# Memory.net
KiCad netlist of a schematic drawn in Altium Designer
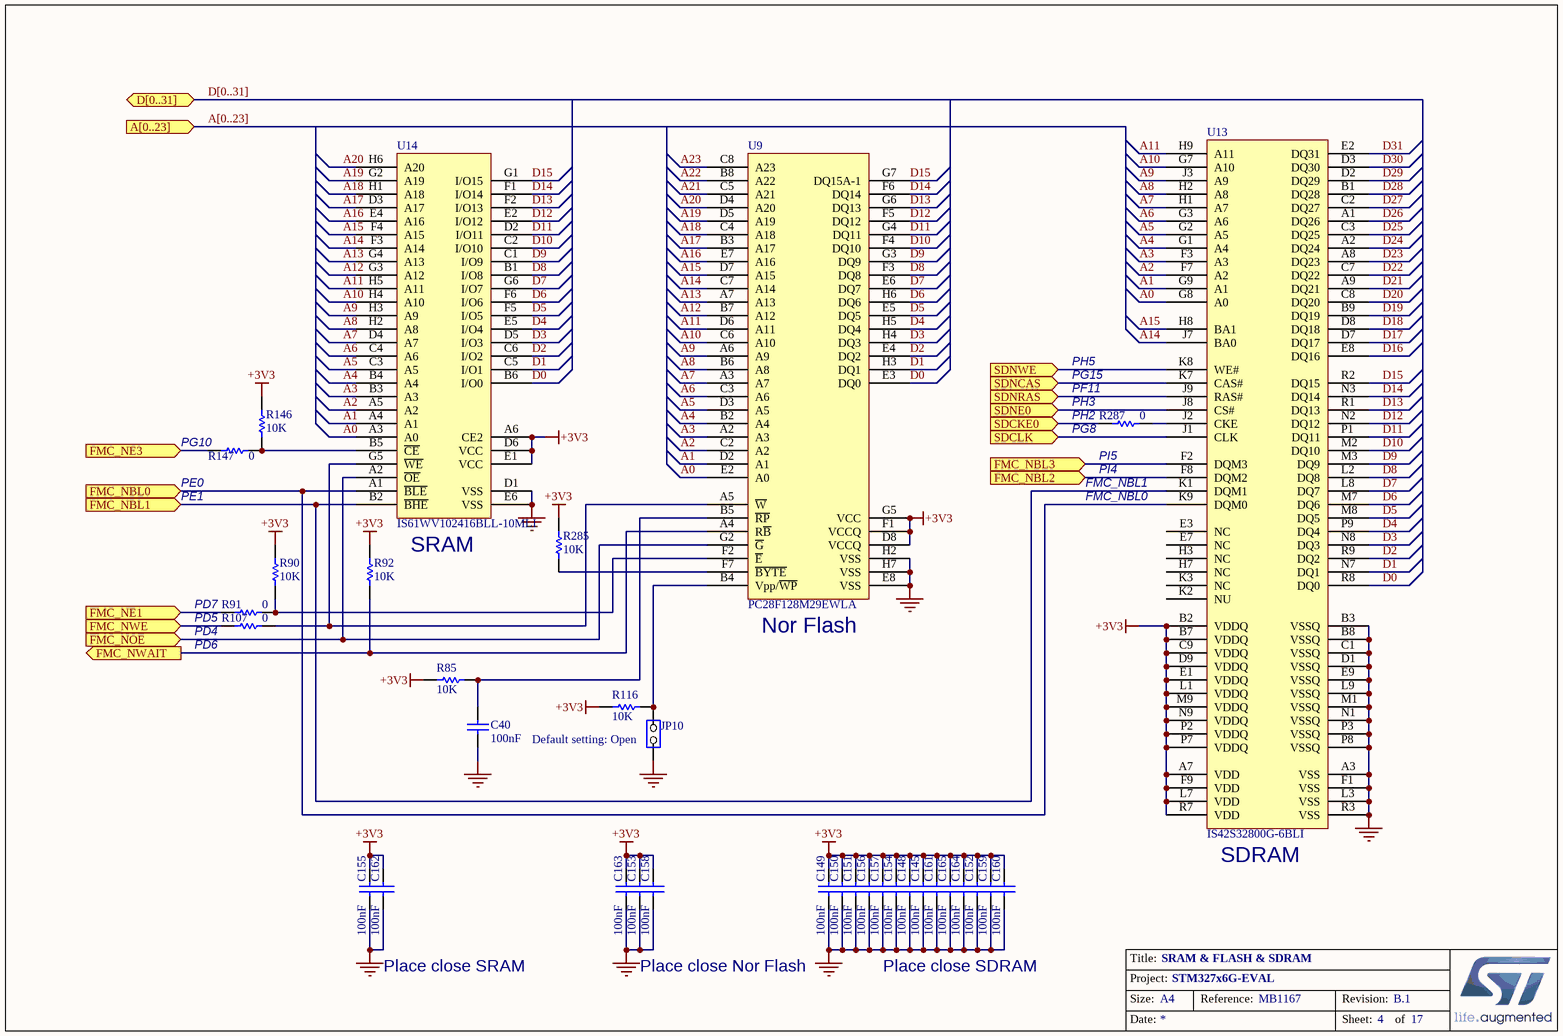
[diagram p0: Memory.SchDoc]

(export (version "E")
  (design (tool "Eeschema 10.0.6"))
  (components
    (comp (ref "C40")
      (value "100nF")
      (footprint "0603C")
      (description "Capacitor")
      (fields (field (name "PUBLISHER") "Altium Limited"))
      (libsource (lib "Miscellaneous Devices") (part "Cap"))
    )
    (comp (ref "C145")
      (value "100nF")
      (footprint "0603C")
      (description "Capacitor")
      (fields (field (name "PUBLISHER") "Altium Limited"))
      (libsource (lib "Miscellaneous Devices") (part "Cap"))
    )
    (comp (ref "C148")
      (value "100nF")
      (footprint "0603C")
      (description "Capacitor")
      (fields (field (name "PUBLISHER") "Altium Limited"))
      (libsource (lib "Miscellaneous Devices") (part "Cap"))
    )
    (comp (ref "C149")
      (value "100nF")
      (footprint "0603C")
      (description "Capacitor")
      (fields (field (name "PUBLISHER") "Altium Limited"))
      (libsource (lib "Miscellaneous Devices") (part "Cap"))
    )
    (comp (ref "C150")
      (value "100nF")
      (footprint "0603C")
      (description "Capacitor")
      (fields (field (name "PUBLISHER") "Altium Limited"))
      (libsource (lib "Miscellaneous Devices") (part "Cap"))
    )
    (comp (ref "C151")
      (value "100nF")
      (footprint "0603C")
      (description "Capacitor")
      (fields (field (name "PUBLISHER") "Altium Limited"))
      (libsource (lib "Miscellaneous Devices") (part "Cap"))
    )
    (comp (ref "C152")
      (value "100nF")
      (footprint "0603C")
      (description "Capacitor")
      (fields (field (name "PUBLISHER") "Altium Limited"))
      (libsource (lib "Miscellaneous Devices") (part "Cap"))
    )
    (comp (ref "C153")
      (value "100nF")
      (footprint "0603C")
      (description "Capacitor")
      (fields (field (name "PUBLISHER") "Altium Limited"))
      (libsource (lib "Miscellaneous Devices") (part "Cap"))
    )
    (comp (ref "C154")
      (value "100nF")
      (footprint "0603C")
      (description "Capacitor")
      (fields (field (name "PUBLISHER") "Altium Limited"))
      (libsource (lib "Miscellaneous Devices") (part "Cap"))
    )
    (comp (ref "C155")
      (value "100nF")
      (footprint "0603C")
      (description "Capacitor")
      (fields (field (name "PUBLISHER") "Altium Limited"))
      (libsource (lib "Miscellaneous Devices") (part "Cap"))
    )
    (comp (ref "C156")
      (value "100nF")
      (footprint "0603C")
      (description "Capacitor")
      (fields (field (name "PUBLISHER") "Altium Limited"))
      (libsource (lib "Miscellaneous Devices") (part "Cap"))
    )
    (comp (ref "C157")
      (value "100nF")
      (footprint "0603C")
      (description "Capacitor")
      (fields (field (name "PUBLISHER") "Altium Limited"))
      (libsource (lib "Miscellaneous Devices") (part "Cap"))
    )
    (comp (ref "C158")
      (value "100nF")
      (footprint "0603C")
      (description "Capacitor")
      (fields (field (name "PUBLISHER") "Altium Limited"))
      (libsource (lib "Miscellaneous Devices") (part "Cap"))
    )
    (comp (ref "C159")
      (value "100nF")
      (footprint "0603C")
      (description "Capacitor")
      (fields (field (name "PUBLISHER") "Altium Limited"))
      (libsource (lib "Miscellaneous Devices") (part "Cap"))
    )
    (comp (ref "C160")
      (value "100nF")
      (footprint "0603C")
      (description "Capacitor")
      (fields (field (name "PUBLISHER") "Altium Limited"))
      (libsource (lib "Miscellaneous Devices") (part "Cap"))
    )
    (comp (ref "C161")
      (value "100nF")
      (footprint "0603C")
      (description "Capacitor")
      (fields (field (name "PUBLISHER") "Altium Limited"))
      (libsource (lib "Miscellaneous Devices") (part "Cap"))
    )
    (comp (ref "C162")
      (value "100nF")
      (footprint "0603C")
      (description "Capacitor")
      (fields (field (name "PUBLISHER") "Altium Limited"))
      (libsource (lib "Miscellaneous Devices") (part "Cap"))
    )
    (comp (ref "C163")
      (value "100nF")
      (footprint "0603C")
      (description "Capacitor")
      (fields (field (name "PUBLISHER") "Altium Limited"))
      (libsource (lib "Miscellaneous Devices") (part "Cap"))
    )
    (comp (ref "C164")
      (value "100nF")
      (footprint "0603C")
      (description "Capacitor")
      (fields (field (name "PUBLISHER") "Altium Limited"))
      (libsource (lib "Miscellaneous Devices") (part "Cap"))
    )
    (comp (ref "C165")
      (value "100nF")
      (footprint "0603C")
      (description "Capacitor")
      (fields (field (name "PUBLISHER") "Altium Limited"))
      (libsource (lib "Miscellaneous Devices") (part "Cap"))
    )
    (comp (ref "JP10") (value "~") (footprint "SIP2") (libsource (lib "*") (part "JP2")))
    (comp (ref "R85")
      (value "10K")
      (footprint "0603R")
      (description "Resistor")
      (fields (field (name "PUBLISHER") "Altium Limited"))
      (libsource (lib "Miscellaneous Devices") (part "Res1"))
    )
    (comp (ref "R90")
      (value "10K")
      (footprint "0603R")
      (description "Resistor")
      (fields (field (name "PUBLISHER") "Altium Limited"))
      (libsource (lib "Miscellaneous Devices") (part "Res1"))
    )
    (comp (ref "R91")
      (value "0")
      (footprint "0603R")
      (description "Resistor")
      (fields (field (name "PUBLISHER") "Altium Limited"))
      (libsource (lib "Miscellaneous Devices") (part "Res1"))
    )
    (comp (ref "R92")
      (value "10K")
      (footprint "0603R")
      (description "Resistor")
      (fields (field (name "PUBLISHER") "Altium Limited"))
      (libsource (lib "Miscellaneous Devices") (part "Res1"))
    )
    (comp (ref "R107")
      (value "0")
      (footprint "0603R")
      (description "Resistor")
      (fields (field (name "PUBLISHER") "Altium Limited"))
      (libsource (lib "Miscellaneous Devices") (part "Res1"))
    )
    (comp (ref "R116")
      (value "10K")
      (footprint "0603R")
      (description "Resistor")
      (fields (field (name "PUBLISHER") "Altium Limited"))
      (libsource (lib "Miscellaneous Devices") (part "Res1"))
    )
    (comp (ref "R146")
      (value "10K")
      (footprint "0603R")
      (description "Resistor")
      (fields (field (name "PUBLISHER") "Altium Limited"))
      (libsource (lib "Miscellaneous Devices") (part "Res1"))
    )
    (comp (ref "R147")
      (value "0")
      (footprint "0603R")
      (description "Resistor")
      (fields (field (name "PUBLISHER") "Altium Limited"))
      (libsource (lib "Miscellaneous Devices") (part "Res1"))
    )
    (comp (ref "R285")
      (value "10K")
      (footprint "0603R")
      (description "Resistor")
      (fields (field (name "PUBLISHER") "Altium Limited"))
      (libsource (lib "Miscellaneous Devices") (part "Res1"))
    )
    (comp (ref "R287")
      (value "0")
      (footprint "0603R")
      (description "Resistor")
      (fields (field (name "PUBLISHER") "Altium Limited"))
      (libsource (lib "Miscellaneous Devices") (part "Res1"))
    )
    (comp (ref "U9")
      (value "PC28F128M29EWLA")
      (footprint "FBGA64_1_11X13")
      (libsource (lib "MB964") (part "M29W128FL70ZA6E"))
    )
    (comp (ref "U13")
      (value "IS42S32800G-6BLI")
      (footprint "FBGA90_0R8_8X13")
      (libsource (lib "mb1045") (part "MT48LC4M32B2B5"))
    )
    (comp (ref "U14")
      (value "IS61WV102416BLL-10MLI")
      (footprint "BGA48_0R75_9X11")
      (libsource (lib "MB901") (part "IS61WV102416BLL-10MLI"))
    )
  )
  (nets
    (net (code "1") (name "+3V3") (class "Default")
      (node (ref "C145") (pin "1") (pinfunction "1_1") (pintype "passive"))
      (node (ref "C148") (pin "1") (pinfunction "1_1") (pintype "passive"))
      (node (ref "C149") (pin "1") (pinfunction "1_1") (pintype "passive"))
      (node (ref "C150") (pin "1") (pinfunction "1_1") (pintype "passive"))
      (node (ref "C151") (pin "1") (pinfunction "1_1") (pintype "passive"))
      (node (ref "C152") (pin "1") (pinfunction "1_1") (pintype "passive"))
      (node (ref "C153") (pin "1") (pinfunction "1_1") (pintype "passive"))
      (node (ref "C154") (pin "1") (pinfunction "1_1") (pintype "passive"))
      (node (ref "C155") (pin "1") (pinfunction "1_1") (pintype "passive"))
      (node (ref "C156") (pin "1") (pinfunction "1_1") (pintype "passive"))
      (node (ref "C157") (pin "1") (pinfunction "1_1") (pintype "passive"))
      (node (ref "C158") (pin "1") (pinfunction "1_1") (pintype "passive"))
      (node (ref "C159") (pin "1") (pinfunction "1_1") (pintype "passive"))
      (node (ref "C160") (pin "1") (pinfunction "1_1") (pintype "passive"))
      (node (ref "C161") (pin "1") (pinfunction "1_1") (pintype "passive"))
      (node (ref "C162") (pin "1") (pinfunction "1_1") (pintype "passive"))
      (node (ref "C163") (pin "1") (pinfunction "1_1") (pintype "passive"))
      (node (ref "C164") (pin "1") (pinfunction "1_1") (pintype "passive"))
      (node (ref "C165") (pin "1") (pinfunction "1_1") (pintype "passive"))
      (node (ref "R116") (pin "2") (pinfunction "2_2") (pintype "passive"))
      (node (ref "R146") (pin "2") (pinfunction "2_2") (pintype "passive"))
      (node (ref "R285") (pin "2") (pinfunction "2_2") (pintype "passive"))
      (node (ref "R85") (pin "1") (pinfunction "1_1") (pintype "passive"))
      (node (ref "R90") (pin "2") (pinfunction "2_2") (pintype "passive"))
      (node (ref "R92") (pin "2") (pinfunction "2_2") (pintype "passive"))
      (node (ref "U13") (pin "A7") (pinfunction "VDD_A7") (pintype "passive"))
      (node (ref "U13") (pin "B2") (pinfunction "VDDQ_B2") (pintype "passive"))
      (node (ref "U13") (pin "B7") (pinfunction "VDDQ_B7") (pintype "passive"))
      (node (ref "U13") (pin "C9") (pinfunction "VDDQ_C9") (pintype "passive"))
      (node (ref "U13") (pin "D9") (pinfunction "VDDQ_D9") (pintype "passive"))
      (node (ref "U13") (pin "E1") (pinfunction "VDDQ_E1") (pintype "passive"))
      (node (ref "U13") (pin "F9") (pinfunction "VDD_F9") (pintype "passive"))
      (node (ref "U13") (pin "L1") (pinfunction "VDDQ_L1") (pintype "passive"))
      (node (ref "U13") (pin "L7") (pinfunction "VDD_L7") (pintype "passive"))
      (node (ref "U13") (pin "M9") (pinfunction "VDDQ_M9") (pintype "passive"))
      (node (ref "U13") (pin "N9") (pinfunction "VDDQ_N9") (pintype "passive"))
      (node (ref "U13") (pin "P2") (pinfunction "VDDQ_P2") (pintype "passive"))
      (node (ref "U13") (pin "P7") (pinfunction "VDDQ_P7") (pintype "passive"))
      (node (ref "U13") (pin "R7") (pinfunction "VDD_R7") (pintype "passive"))
      (node (ref "U14") (pin "A6") (pinfunction "CE2_A6") (pintype "passive"))
      (node (ref "U14") (pin "D6") (pinfunction "VCC_D6") (pintype "passive"))
      (node (ref "U14") (pin "E1") (pinfunction "VCC_E1") (pintype "passive"))
      (node (ref "U9") (pin "D8") (pinfunction "VCCQ_D8") (pintype "passive"))
      (node (ref "U9") (pin "F1") (pinfunction "VCCQ_F1") (pintype "passive"))
      (node (ref "U9") (pin "G5") (pinfunction "VCC_G5") (pintype "passive"))
    )
    (net (code "2") (name "/A0") (class "Default")
      (node (ref "U13") (pin "G8") (pinfunction "A0_G8") (pintype "passive"))
      (node (ref "U14") (pin "A3") (pinfunction "A0_A3") (pintype "passive"))
      (node (ref "U9") (pin "E2") (pinfunction "A0_E2") (pintype "passive"))
    )
    (net (code "3") (name "/A1") (class "Default")
      (node (ref "U13") (pin "G9") (pinfunction "A1_G9") (pintype "passive"))
      (node (ref "U14") (pin "A4") (pinfunction "A1_A4") (pintype "passive"))
      (node (ref "U9") (pin "D2") (pinfunction "A1_D2") (pintype "passive"))
    )
    (net (code "4") (name "/A2") (class "Default")
      (node (ref "U13") (pin "F7") (pinfunction "A2_F7") (pintype "passive"))
      (node (ref "U14") (pin "A5") (pinfunction "A2_A5") (pintype "passive"))
      (node (ref "U9") (pin "C2") (pinfunction "A2_C2") (pintype "passive"))
    )
    (net (code "5") (name "/A3") (class "Default")
      (node (ref "U13") (pin "F3") (pinfunction "A3_F3") (pintype "passive"))
      (node (ref "U14") (pin "B3") (pinfunction "A3_B3") (pintype "passive"))
      (node (ref "U9") (pin "A2") (pinfunction "A3_A2") (pintype "passive"))
    )
    (net (code "6") (name "/A4") (class "Default")
      (node (ref "U13") (pin "G1") (pinfunction "A4_G1") (pintype "passive"))
      (node (ref "U14") (pin "B4") (pinfunction "A4_B4") (pintype "passive"))
      (node (ref "U9") (pin "B2") (pinfunction "A4_B2") (pintype "passive"))
    )
    (net (code "7") (name "/A5") (class "Default")
      (node (ref "U13") (pin "G2") (pinfunction "A5_G2") (pintype "passive"))
      (node (ref "U14") (pin "C3") (pinfunction "A5_C3") (pintype "passive"))
      (node (ref "U9") (pin "D3") (pinfunction "A5_D3") (pintype "passive"))
    )
    (net (code "8") (name "/A6") (class "Default")
      (node (ref "U13") (pin "G3") (pinfunction "A6_G3") (pintype "passive"))
      (node (ref "U14") (pin "C4") (pinfunction "A6_C4") (pintype "passive"))
      (node (ref "U9") (pin "C3") (pinfunction "A6_C3") (pintype "passive"))
    )
    (net (code "9") (name "/A7") (class "Default")
      (node (ref "U13") (pin "H1") (pinfunction "A7_H1") (pintype "passive"))
      (node (ref "U14") (pin "D4") (pinfunction "A7_D4") (pintype "passive"))
      (node (ref "U9") (pin "A3") (pinfunction "A7_A3") (pintype "passive"))
    )
    (net (code "10") (name "/A8") (class "Default")
      (node (ref "U13") (pin "H2") (pinfunction "A8_H2") (pintype "passive"))
      (node (ref "U14") (pin "H2") (pinfunction "A8_H2") (pintype "passive"))
      (node (ref "U9") (pin "B6") (pinfunction "A8_B6") (pintype "passive"))
    )
    (net (code "11") (name "/A9") (class "Default")
      (node (ref "U13") (pin "J3") (pinfunction "A9_J3") (pintype "passive"))
      (node (ref "U14") (pin "H3") (pinfunction "A9_H3") (pintype "passive"))
      (node (ref "U9") (pin "A6") (pinfunction "A9_A6") (pintype "passive"))
    )
    (net (code "12") (name "/A10") (class "Default")
      (node (ref "U13") (pin "G7") (pinfunction "A10_G7") (pintype "passive"))
      (node (ref "U14") (pin "H4") (pinfunction "A10_H4") (pintype "passive"))
      (node (ref "U9") (pin "C6") (pinfunction "A10_C6") (pintype "passive"))
    )
    (net (code "13") (name "/A11") (class "Default")
      (node (ref "U13") (pin "H9") (pinfunction "A11_H9") (pintype "passive"))
      (node (ref "U14") (pin "H5") (pinfunction "A11_H5") (pintype "passive"))
      (node (ref "U9") (pin "D6") (pinfunction "A11_D6") (pintype "passive"))
    )
    (net (code "14") (name "/A12") (class "Default")
      (node (ref "U14") (pin "G3") (pinfunction "A12_G3") (pintype "passive"))
      (node (ref "U9") (pin "B7") (pinfunction "A12_B7") (pintype "passive"))
    )
    (net (code "15") (name "/A13") (class "Default")
      (node (ref "U14") (pin "G4") (pinfunction "A13_G4") (pintype "passive"))
      (node (ref "U9") (pin "A7") (pinfunction "A13_A7") (pintype "passive"))
    )
    (net (code "16") (name "/A14") (class "Default")
      (node (ref "U13") (pin "J7") (pinfunction "BA0_J7") (pintype "passive"))
      (node (ref "U14") (pin "F3") (pinfunction "A14_F3") (pintype "passive"))
      (node (ref "U9") (pin "C7") (pinfunction "A14_C7") (pintype "passive"))
    )
    (net (code "17") (name "/A15") (class "Default")
      (node (ref "U13") (pin "H8") (pinfunction "BA1_H8") (pintype "passive"))
      (node (ref "U14") (pin "F4") (pinfunction "A15_F4") (pintype "passive"))
      (node (ref "U9") (pin "D7") (pinfunction "A15_D7") (pintype "passive"))
    )
    (net (code "18") (name "/A16") (class "Default")
      (node (ref "U14") (pin "E4") (pinfunction "A16_E4") (pintype "passive"))
      (node (ref "U9") (pin "E7") (pinfunction "A16_E7") (pintype "passive"))
    )
    (net (code "19") (name "/A17") (class "Default")
      (node (ref "U14") (pin "D3") (pinfunction "A17_D3") (pintype "passive"))
      (node (ref "U9") (pin "B3") (pinfunction "A17_B3") (pintype "passive"))
    )
    (net (code "20") (name "/A18") (class "Default")
      (node (ref "U14") (pin "H1") (pinfunction "A18_H1") (pintype "passive"))
      (node (ref "U9") (pin "C4") (pinfunction "A18_C4") (pintype "passive"))
    )
    (net (code "21") (name "/A19") (class "Default")
      (node (ref "U14") (pin "G2") (pinfunction "A19_G2") (pintype "passive"))
      (node (ref "U9") (pin "D5") (pinfunction "A19_D5") (pintype "passive"))
    )
    (net (code "22") (name "/A20") (class "Default")
      (node (ref "U14") (pin "H6") (pinfunction "A20_H6") (pintype "passive"))
      (node (ref "U9") (pin "D4") (pinfunction "A20_D4") (pintype "passive"))
    )
    (net (code "23") (name "/A21") (class "Default")
      (node (ref "U9") (pin "C5") (pinfunction "A21_C5") (pintype "passive"))
    )
    (net (code "24") (name "/A22") (class "Default")
      (node (ref "U9") (pin "B8") (pinfunction "A22_B8") (pintype "passive"))
    )
    (net (code "25") (name "/A23") (class "Default")
      (node (ref "U9") (pin "C8") (pinfunction "A23_C8") (pintype "passive"))
    )
    (net (code "27") (name "/D0") (class "Default")
      (node (ref "U13") (pin "R8") (pinfunction "DQ0_R8") (pintype "passive"))
      (node (ref "U14") (pin "B6") (pinfunction "I/O0_B6") (pintype "passive"))
      (node (ref "U9") (pin "E3") (pinfunction "DQ0_E3") (pintype "passive"))
    )
    (net (code "28") (name "/D1") (class "Default")
      (node (ref "U13") (pin "N7") (pinfunction "DQ1_N7") (pintype "passive"))
      (node (ref "U14") (pin "C5") (pinfunction "I/O1_C5") (pintype "passive"))
      (node (ref "U9") (pin "H3") (pinfunction "DQ1_H3") (pintype "passive"))
    )
    (net (code "29") (name "/D2") (class "Default")
      (node (ref "U13") (pin "R9") (pinfunction "DQ2_R9") (pintype "passive"))
      (node (ref "U14") (pin "C6") (pinfunction "I/O2_C6") (pintype "passive"))
      (node (ref "U9") (pin "E4") (pinfunction "DQ2_E4") (pintype "passive"))
    )
    (net (code "30") (name "/D3") (class "Default")
      (node (ref "U13") (pin "N8") (pinfunction "DQ3_N8") (pintype "passive"))
      (node (ref "U14") (pin "D5") (pinfunction "I/O3_D5") (pintype "passive"))
      (node (ref "U9") (pin "H4") (pinfunction "DQ3_H4") (pintype "passive"))
    )
    (net (code "31") (name "/D4") (class "Default")
      (node (ref "U13") (pin "P9") (pinfunction "DQ4_P9") (pintype "passive"))
      (node (ref "U14") (pin "E5") (pinfunction "I/O4_E5") (pintype "passive"))
      (node (ref "U9") (pin "H5") (pinfunction "DQ4_H5") (pintype "passive"))
    )
    (net (code "32") (name "/D5") (class "Default")
      (node (ref "U13") (pin "M8") (pinfunction "DQ5_M8") (pintype "passive"))
      (node (ref "U14") (pin "F5") (pinfunction "I/O5_F5") (pintype "passive"))
      (node (ref "U9") (pin "E5") (pinfunction "DQ5_E5") (pintype "passive"))
    )
    (net (code "33") (name "/D6") (class "Default")
      (node (ref "U13") (pin "M7") (pinfunction "DQ6_M7") (pintype "passive"))
      (node (ref "U14") (pin "F6") (pinfunction "I/O6_F6") (pintype "passive"))
      (node (ref "U9") (pin "H6") (pinfunction "DQ6_H6") (pintype "passive"))
    )
    (net (code "34") (name "/D7") (class "Default")
      (node (ref "U13") (pin "L8") (pinfunction "DQ7_L8") (pintype "passive"))
      (node (ref "U14") (pin "G6") (pinfunction "I/O7_G6") (pintype "passive"))
      (node (ref "U9") (pin "E6") (pinfunction "DQ7_E6") (pintype "passive"))
    )
    (net (code "35") (name "/D8") (class "Default")
      (node (ref "U13") (pin "L2") (pinfunction "DQ8_L2") (pintype "passive"))
      (node (ref "U14") (pin "B1") (pinfunction "I/O8_B1") (pintype "passive"))
      (node (ref "U9") (pin "F3") (pinfunction "DQ8_F3") (pintype "passive"))
    )
    (net (code "36") (name "/D9") (class "Default")
      (node (ref "U13") (pin "M3") (pinfunction "DQ9_M3") (pintype "passive"))
      (node (ref "U14") (pin "C1") (pinfunction "I/O9_C1") (pintype "passive"))
      (node (ref "U9") (pin "G3") (pinfunction "DQ9_G3") (pintype "passive"))
    )
    (net (code "37") (name "/D10") (class "Default")
      (node (ref "U13") (pin "M2") (pinfunction "DQ10_M2") (pintype "passive"))
      (node (ref "U14") (pin "C2") (pinfunction "I/O10_C2") (pintype "passive"))
      (node (ref "U9") (pin "F4") (pinfunction "DQ10_F4") (pintype "passive"))
    )
    (net (code "38") (name "/D11") (class "Default")
      (node (ref "U13") (pin "P1") (pinfunction "DQ11_P1") (pintype "passive"))
      (node (ref "U14") (pin "D2") (pinfunction "I/O11_D2") (pintype "passive"))
      (node (ref "U9") (pin "G4") (pinfunction "DQ11_G4") (pintype "passive"))
    )
    (net (code "39") (name "/D12") (class "Default")
      (node (ref "U13") (pin "N2") (pinfunction "DQ12_N2") (pintype "passive"))
      (node (ref "U14") (pin "E2") (pinfunction "I/O12_E2") (pintype "passive"))
      (node (ref "U9") (pin "F5") (pinfunction "DQ12_F5") (pintype "passive"))
    )
    (net (code "40") (name "/D13") (class "Default")
      (node (ref "U13") (pin "R1") (pinfunction "DQ13_R1") (pintype "passive"))
      (node (ref "U14") (pin "F2") (pinfunction "I/O13_F2") (pintype "passive"))
      (node (ref "U9") (pin "G6") (pinfunction "DQ13_G6") (pintype "passive"))
    )
    (net (code "41") (name "/D14") (class "Default")
      (node (ref "U13") (pin "N3") (pinfunction "DQ14_N3") (pintype "passive"))
      (node (ref "U14") (pin "F1") (pinfunction "I/O14_F1") (pintype "passive"))
      (node (ref "U9") (pin "F6") (pinfunction "DQ14_F6") (pintype "passive"))
    )
    (net (code "42") (name "/D15") (class "Default")
      (node (ref "U13") (pin "R2") (pinfunction "DQ15_R2") (pintype "passive"))
      (node (ref "U14") (pin "G1") (pinfunction "I/O15_G1") (pintype "passive"))
      (node (ref "U9") (pin "G7") (pinfunction "DQ15A-1_G7") (pintype "passive"))
    )
    (net (code "43") (name "/D16") (class "Default")
      (node (ref "U13") (pin "E8") (pinfunction "DQ16_E8") (pintype "passive"))
    )
    (net (code "44") (name "/D17") (class "Default")
      (node (ref "U13") (pin "D7") (pinfunction "DQ17_D7") (pintype "passive"))
    )
    (net (code "45") (name "/D18") (class "Default")
      (node (ref "U13") (pin "D8") (pinfunction "DQ18_D8") (pintype "passive"))
    )
    (net (code "46") (name "/D19") (class "Default")
      (node (ref "U13") (pin "B9") (pinfunction "DQ19_B9") (pintype "passive"))
    )
    (net (code "47") (name "/D20") (class "Default")
      (node (ref "U13") (pin "C8") (pinfunction "DQ20_C8") (pintype "passive"))
    )
    (net (code "48") (name "/D21") (class "Default")
      (node (ref "U13") (pin "A9") (pinfunction "DQ21_A9") (pintype "passive"))
    )
    (net (code "49") (name "/D22") (class "Default")
      (node (ref "U13") (pin "C7") (pinfunction "DQ22_C7") (pintype "passive"))
    )
    (net (code "50") (name "/D23") (class "Default")
      (node (ref "U13") (pin "A8") (pinfunction "DQ23_A8") (pintype "passive"))
    )
    (net (code "51") (name "/D24") (class "Default")
      (node (ref "U13") (pin "A2") (pinfunction "DQ24_A2") (pintype "passive"))
    )
    (net (code "52") (name "/D25") (class "Default")
      (node (ref "U13") (pin "C3") (pinfunction "DQ25_C3") (pintype "passive"))
    )
    (net (code "53") (name "/D26") (class "Default")
      (node (ref "U13") (pin "A1") (pinfunction "DQ26_A1") (pintype "passive"))
    )
    (net (code "54") (name "/D27") (class "Default")
      (node (ref "U13") (pin "C2") (pinfunction "DQ27_C2") (pintype "passive"))
    )
    (net (code "55") (name "/D28") (class "Default")
      (node (ref "U13") (pin "B1") (pinfunction "DQ28_B1") (pintype "passive"))
    )
    (net (code "56") (name "/D29") (class "Default")
      (node (ref "U13") (pin "D2") (pinfunction "DQ29_D2") (pintype "passive"))
    )
    (net (code "57") (name "/D30") (class "Default")
      (node (ref "U13") (pin "D3") (pinfunction "DQ30_D3") (pintype "passive"))
    )
    (net (code "58") (name "/D31") (class "Default")
      (node (ref "U13") (pin "E2") (pinfunction "DQ31_E2") (pintype "passive"))
    )
    (net (code "60") (name "/FMC_NBL0") (class "Default")
      (node (ref "U13") (pin "K9") (pinfunction "DQM0_K9") (pintype "passive"))
      (node (ref "U14") (pin "A1") (pinfunction "~{BLE}_A1") (pintype "passive"))
    )
    (net (code "61") (name "/FMC_NBL1") (class "Default")
      (node (ref "U13") (pin "K1") (pinfunction "DQM1_K1") (pintype "passive"))
      (node (ref "U14") (pin "B2") (pinfunction "~{BHE}_B2") (pintype "passive"))
    )
    (net (code "62") (name "/FMC_NBL2") (class "Default")
      (node (ref "U13") (pin "F8") (pinfunction "DQM2_F8") (pintype "passive"))
    )
    (net (code "63") (name "/FMC_NBL3") (class "Default")
      (node (ref "U13") (pin "F2") (pinfunction "DQM3_F2") (pintype "passive"))
    )
    (net (code "64") (name "/FMC_NE1") (class "Default")
      (node (ref "R91") (pin "2") (pinfunction "2_2") (pintype "passive"))
    )
    (net (code "65") (name "/FMC_NE3") (class "Default")
      (node (ref "R147") (pin "2") (pinfunction "2_2") (pintype "passive"))
    )
    (net (code "66") (name "/FMC_NOE") (class "Default")
      (node (ref "U14") (pin "A2") (pinfunction "~{OE}_A2") (pintype "passive"))
      (node (ref "U9") (pin "G2") (pinfunction "~{G}_G2") (pintype "passive"))
    )
    (net (code "67") (name "/FMC_NWAIT") (class "Default")
      (node (ref "R92") (pin "1") (pinfunction "1_1") (pintype "passive"))
      (node (ref "U9") (pin "A4") (pinfunction "R~{B}_A4") (pintype "passive"))
    )
    (net (code "68") (name "/FMC_NWE") (class "Default")
      (node (ref "R107") (pin "2") (pinfunction "2_2") (pintype "passive"))
    )
    (net (code "69") (name "/SDCKE0") (class "Default")
      (node (ref "R287") (pin "2") (pinfunction "2_2") (pintype "passive"))
    )
    (net (code "70") (name "/SDCLK") (class "Default")
      (node (ref "U13") (pin "J1") (pinfunction "CLK_J1") (pintype "passive"))
    )
    (net (code "71") (name "/SDNCAS") (class "Default")
      (node (ref "U13") (pin "K7") (pinfunction "CAS#_K7") (pintype "passive"))
    )
    (net (code "72") (name "/SDNE0") (class "Default")
      (node (ref "U13") (pin "J8") (pinfunction "CS#_J8") (pintype "passive"))
    )
    (net (code "73") (name "/SDNRAS") (class "Default")
      (node (ref "U13") (pin "J9") (pinfunction "RAS#_J9") (pintype "passive"))
    )
    (net (code "74") (name "/SDNWE") (class "Default")
      (node (ref "U13") (pin "K8") (pinfunction "WE#_K8") (pintype "passive"))
    )
    (net (code "75") (name "GND") (class "Default")
      (node (ref "C145") (pin "2") (pinfunction "2_2") (pintype "passive"))
      (node (ref "C148") (pin "2") (pinfunction "2_2") (pintype "passive"))
      (node (ref "C149") (pin "2") (pinfunction "2_2") (pintype "passive"))
      (node (ref "C150") (pin "2") (pinfunction "2_2") (pintype "passive"))
      (node (ref "C151") (pin "2") (pinfunction "2_2") (pintype "passive"))
      (node (ref "C152") (pin "2") (pinfunction "2_2") (pintype "passive"))
      (node (ref "C153") (pin "2") (pinfunction "2_2") (pintype "passive"))
      (node (ref "C154") (pin "2") (pinfunction "2_2") (pintype "passive"))
      (node (ref "C155") (pin "2") (pinfunction "2_2") (pintype "passive"))
      (node (ref "C156") (pin "2") (pinfunction "2_2") (pintype "passive"))
      (node (ref "C157") (pin "2") (pinfunction "2_2") (pintype "passive"))
      (node (ref "C158") (pin "2") (pinfunction "2_2") (pintype "passive"))
      (node (ref "C159") (pin "2") (pinfunction "2_2") (pintype "passive"))
      (node (ref "C160") (pin "2") (pinfunction "2_2") (pintype "passive"))
      (node (ref "C161") (pin "2") (pinfunction "2_2") (pintype "passive"))
      (node (ref "C162") (pin "2") (pinfunction "2_2") (pintype "passive"))
      (node (ref "C163") (pin "2") (pinfunction "2_2") (pintype "passive"))
      (node (ref "C164") (pin "2") (pinfunction "2_2") (pintype "passive"))
      (node (ref "C165") (pin "2") (pinfunction "2_2") (pintype "passive"))
      (node (ref "C40") (pin "2") (pinfunction "2_2") (pintype "passive"))
      (node (ref "JP10") (pin "1") (pinfunction "COMMON_1") (pintype "passive"))
      (node (ref "U13") (pin "A3") (pinfunction "VSS_A3") (pintype "passive"))
      (node (ref "U13") (pin "B3") (pinfunction "VSSQ_B3") (pintype "passive"))
      (node (ref "U13") (pin "B8") (pinfunction "VSSQ_B8") (pintype "passive"))
      (node (ref "U13") (pin "C1") (pinfunction "VSSQ_C1") (pintype "passive"))
      (node (ref "U13") (pin "D1") (pinfunction "VSSQ_D1") (pintype "passive"))
      (node (ref "U13") (pin "E9") (pinfunction "VSSQ_E9") (pintype "passive"))
      (node (ref "U13") (pin "F1") (pinfunction "VSS_F1") (pintype "passive"))
      (node (ref "U13") (pin "L3") (pinfunction "VSS_L3") (pintype "passive"))
      (node (ref "U13") (pin "L9") (pinfunction "VSSQ_L9") (pintype "passive"))
      (node (ref "U13") (pin "M1") (pinfunction "VSSQ_M1") (pintype "passive"))
      (node (ref "U13") (pin "N1") (pinfunction "VSSQ_N1") (pintype "passive"))
      (node (ref "U13") (pin "P3") (pinfunction "VSSQ_P3") (pintype "passive"))
      (node (ref "U13") (pin "P8") (pinfunction "VSSQ_P8") (pintype "passive"))
      (node (ref "U13") (pin "R3") (pinfunction "VSS_R3") (pintype "passive"))
      (node (ref "U14") (pin "D1") (pinfunction "VSS_D1") (pintype "passive"))
      (node (ref "U14") (pin "E6") (pinfunction "VSS_E6") (pintype "passive"))
      (node (ref "U9") (pin "E8") (pinfunction "VSS_E8") (pintype "passive"))
      (node (ref "U9") (pin "H2") (pinfunction "VSS_H2") (pintype "passive"))
      (node (ref "U9") (pin "H7") (pinfunction "VSS_H7") (pintype "passive"))
    )
    (net (code "76") (name "Net-(JP10-NO)") (class "Default")
      (node (ref "JP10") (pin "2") (pinfunction "NO_2") (pintype "passive"))
      (node (ref "R116") (pin "1") (pinfunction "1_1") (pintype "passive"))
      (node (ref "U9") (pin "B4") (pinfunction "Vpp/~{WP}_B4") (pintype "passive"))
    )
    (net (code "77") (name "Net-(U9-~{BYTE})") (class "Default")
      (node (ref "R285") (pin "1") (pinfunction "1_1") (pintype "passive"))
      (node (ref "U9") (pin "F7") (pinfunction "~{BYTE}_F7") (pintype "passive"))
    )
    (net (code "78") (name "Net-(U9-~{E})") (class "Default")
      (node (ref "R90") (pin "1") (pinfunction "1_1") (pintype "passive"))
      (node (ref "R91") (pin "1") (pinfunction "1_1") (pintype "passive"))
      (node (ref "U9") (pin "F2") (pinfunction "~{E}_F2") (pintype "passive"))
    )
    (net (code "79") (name "Net-(U9-~{RP})") (class "Default")
      (node (ref "C40") (pin "1") (pinfunction "1_1") (pintype "passive"))
      (node (ref "R85") (pin "2") (pinfunction "2_2") (pintype "passive"))
      (node (ref "U9") (pin "B5") (pinfunction "~{RP}_B5") (pintype "passive"))
    )
    (net (code "80") (name "Net-(U13-CKE)") (class "Default")
      (node (ref "R287") (pin "1") (pinfunction "1_1") (pintype "passive"))
      (node (ref "U13") (pin "J2") (pinfunction "CKE_J2") (pintype "passive"))
    )
    (net (code "81") (name "Net-(U14-~{CE})") (class "Default")
      (node (ref "R146") (pin "1") (pinfunction "1_1") (pintype "passive"))
      (node (ref "R147") (pin "1") (pinfunction "1_1") (pintype "passive"))
      (node (ref "U14") (pin "B5") (pinfunction "~{CE}_B5") (pintype "passive"))
    )
    (net (code "82") (name "Net-(U14-~{WE})") (class "Default")
      (node (ref "R107") (pin "1") (pinfunction "1_1") (pintype "passive"))
      (node (ref "U14") (pin "G5") (pinfunction "~{WE}_G5") (pintype "passive"))
      (node (ref "U9") (pin "A5") (pinfunction "~{W}_A5") (pintype "passive"))
    )
    (net (code "83") (name "unconnected-(U13-NC-PadE3)") (class "Default")
      (node (ref "U13") (pin "E3") (pinfunction "NC_E3") (pintype "passive"))
    )
    (net (code "84") (name "unconnected-(U13-NC-PadE7)") (class "Default")
      (node (ref "U13") (pin "E7") (pinfunction "NC_E7") (pintype "passive"))
    )
    (net (code "85") (name "unconnected-(U13-NC-PadH3)") (class "Default")
      (node (ref "U13") (pin "H3") (pinfunction "NC_H3") (pintype "passive"))
    )
    (net (code "86") (name "unconnected-(U13-NC-PadH7)") (class "Default")
      (node (ref "U13") (pin "H7") (pinfunction "NC_H7") (pintype "passive"))
    )
    (net (code "87") (name "unconnected-(U13-NC-PadK3)") (class "Default")
      (node (ref "U13") (pin "K3") (pinfunction "NC_K3") (pintype "passive"))
    )
    (net (code "88") (name "unconnected-(U13-NU-PadK2)") (class "Default")
      (node (ref "U13") (pin "K2") (pinfunction "NU_K2") (pintype "passive"))
    )
  )
)
